# Control_Board.net
KiCad netlist of a schematic drawn in EAGLE
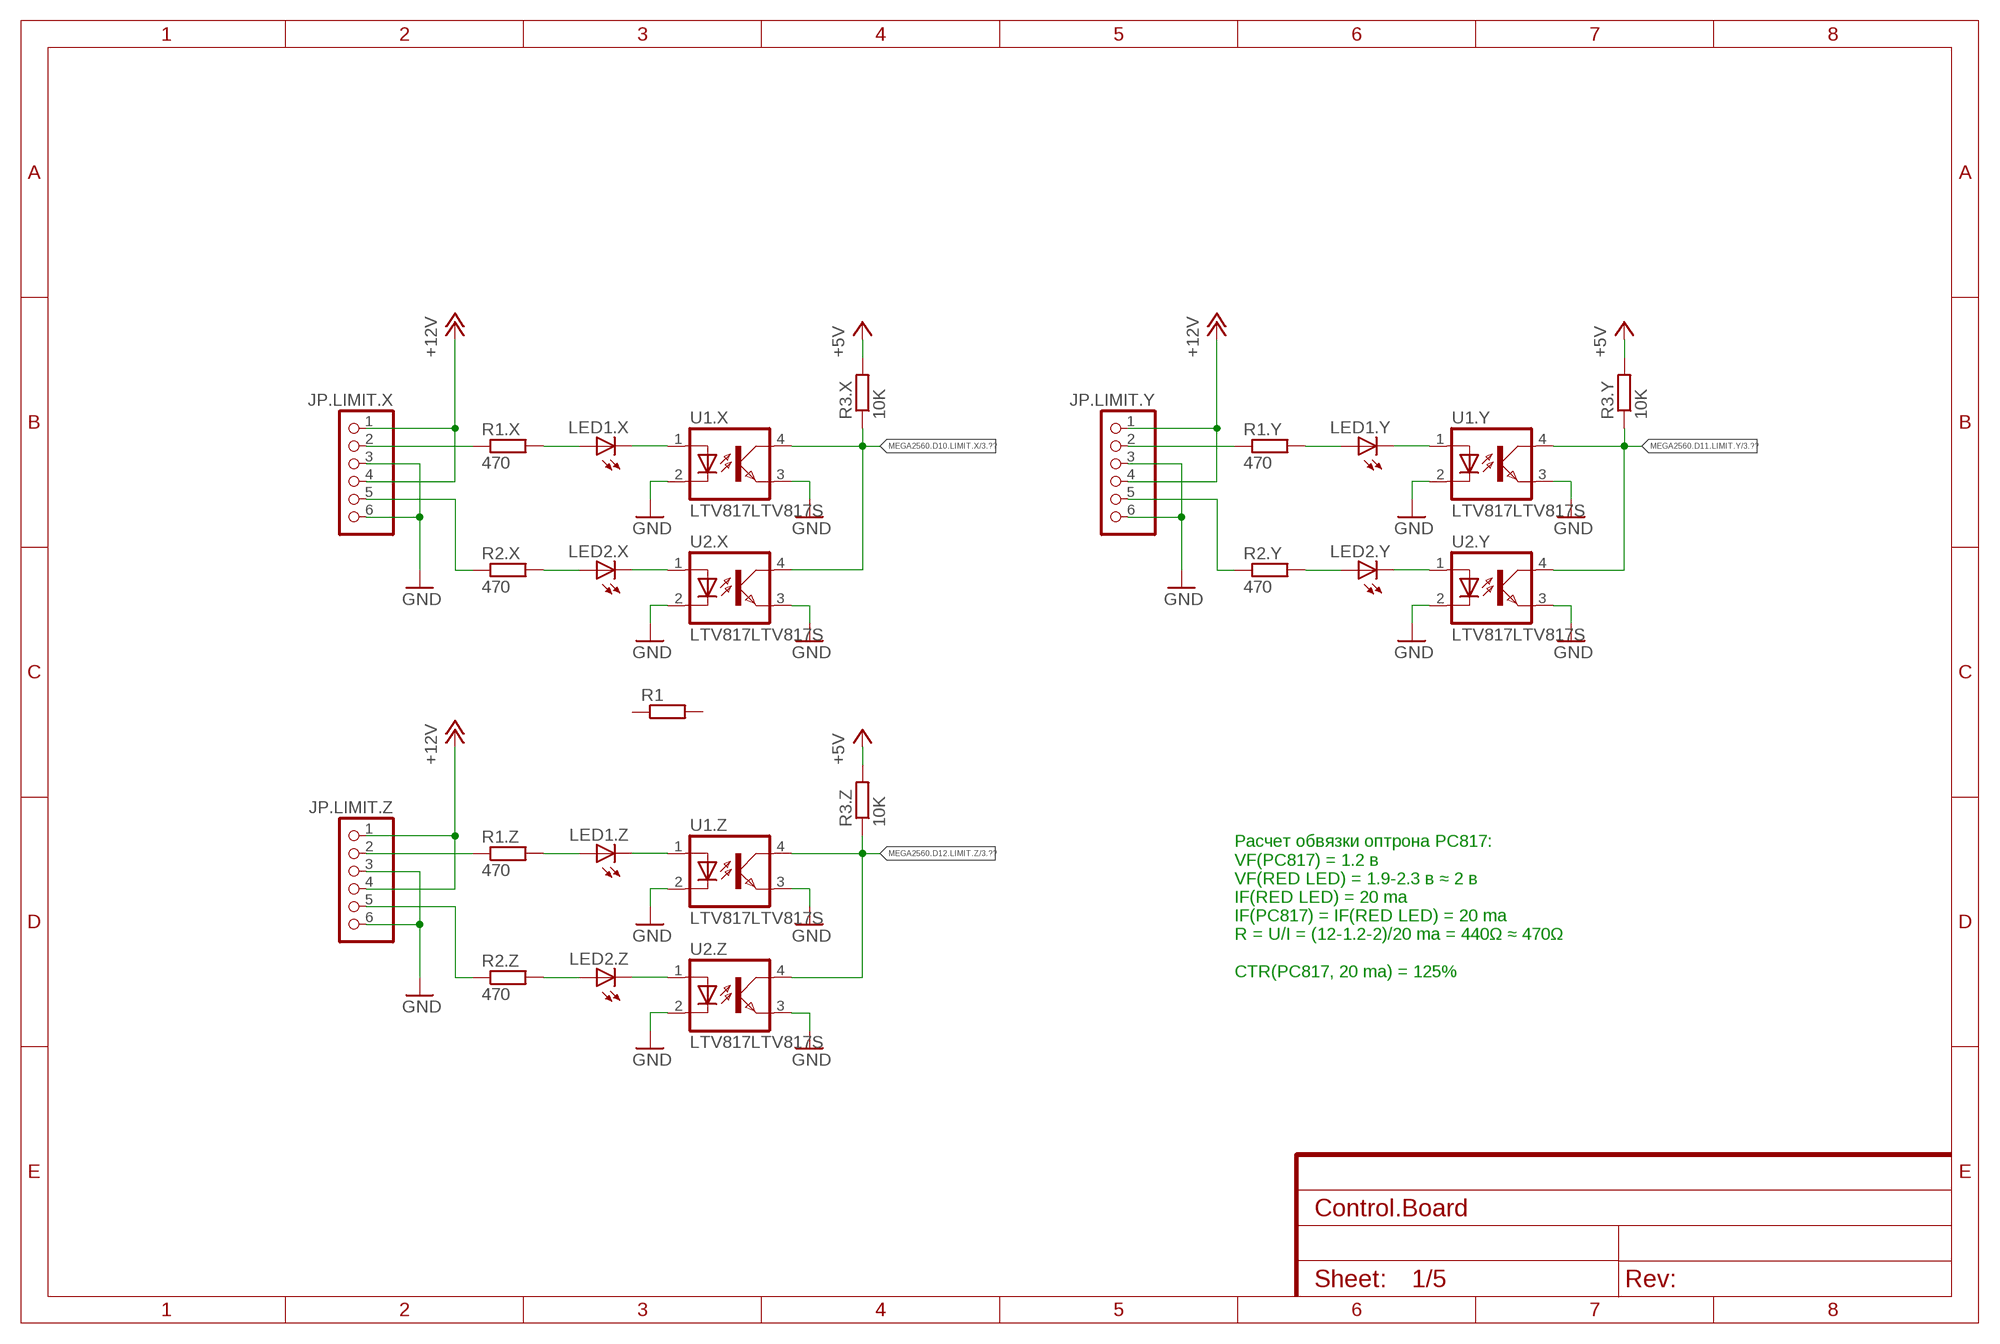
[diagram p0: schematic, sheet 1]
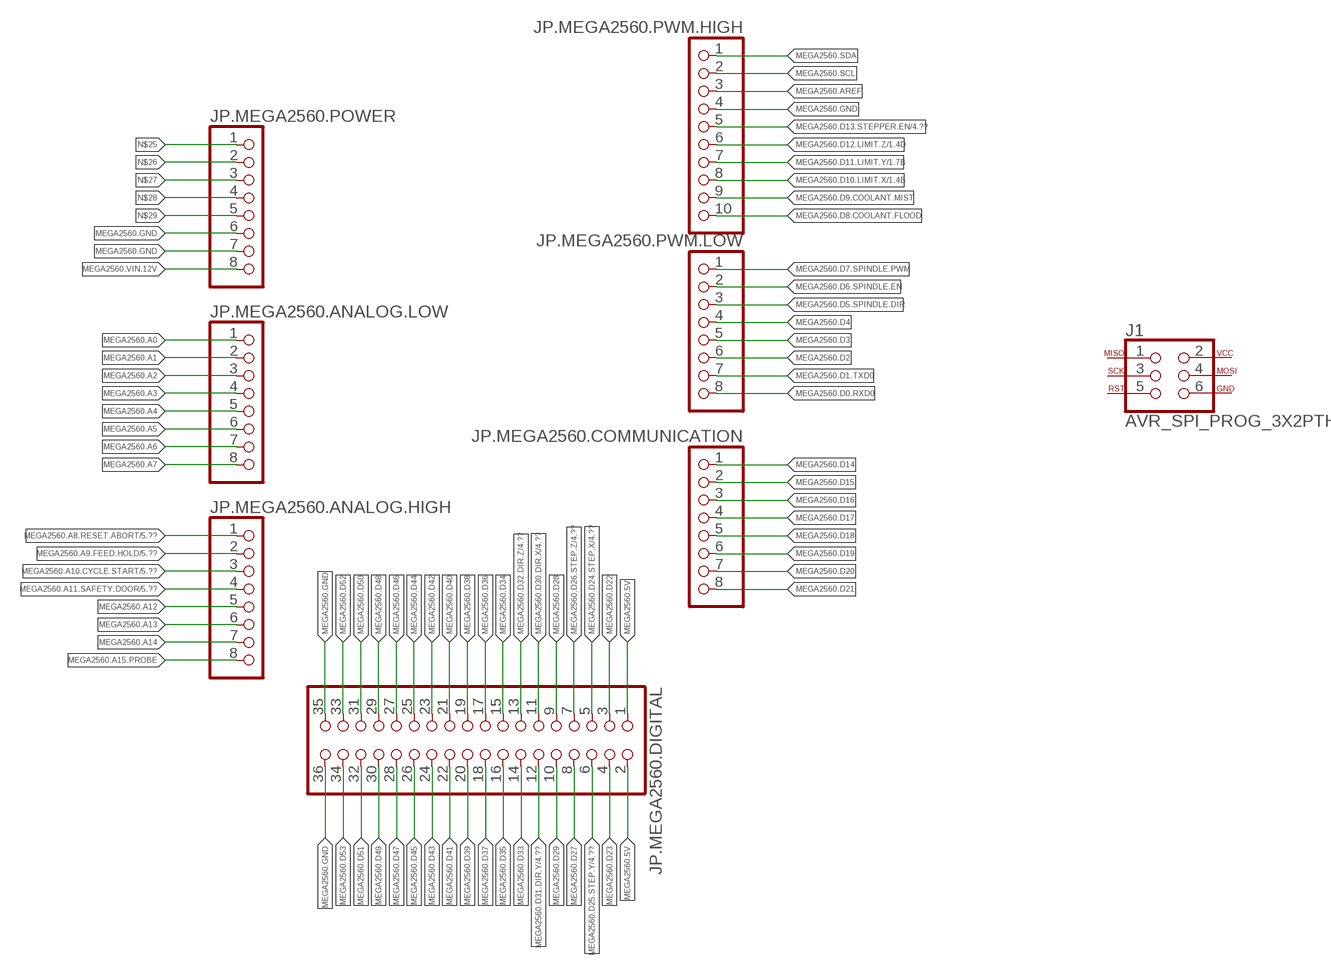
[diagram p1: schematic, sheet 3]
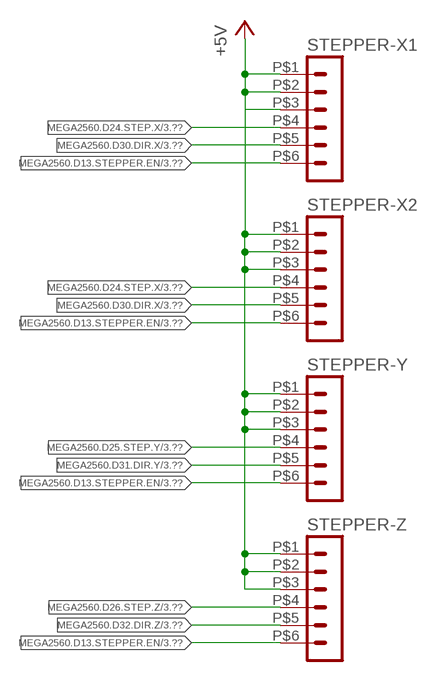
[diagram p2: schematic, sheet 4]
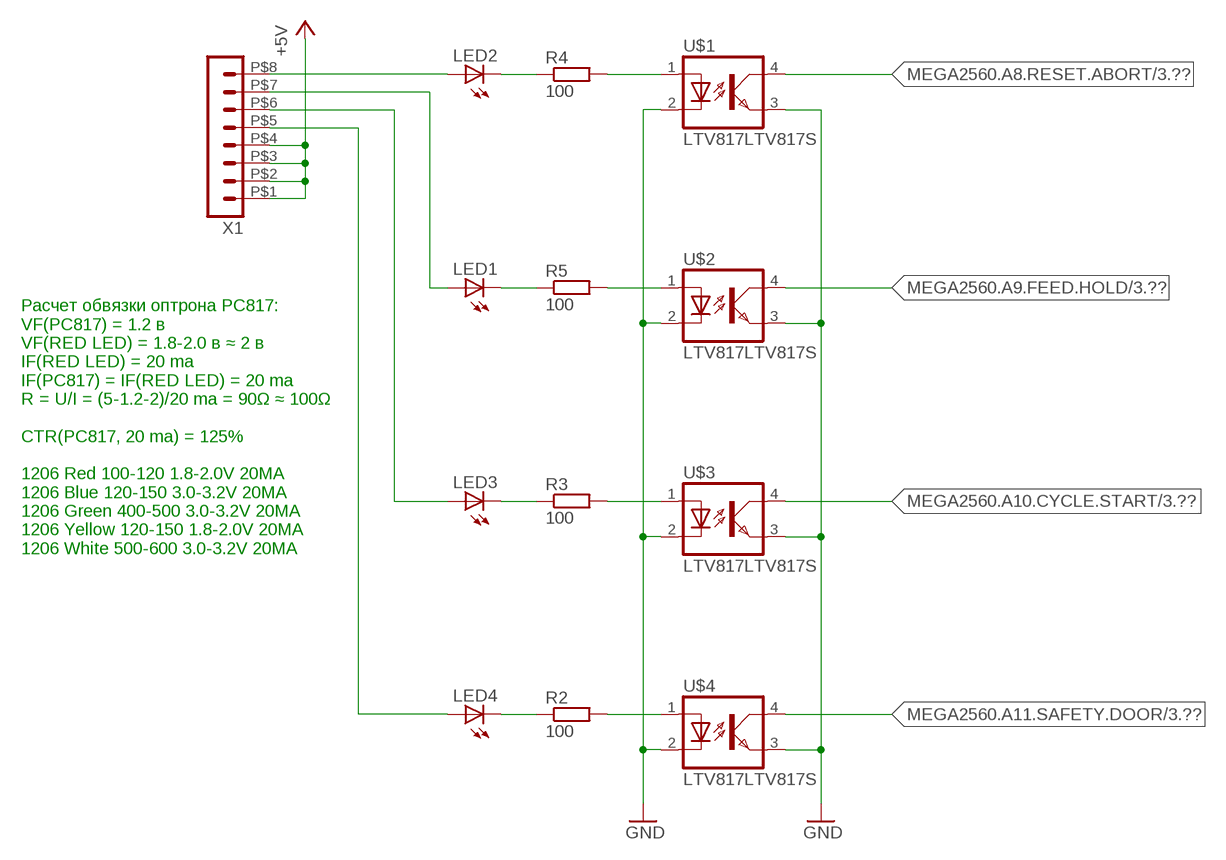
[diagram p3: schematic, sheet 5]

(export (version "E")
  (design (tool "Eeschema 10.0.6"))
  (components
    (comp (ref "LED1")
      (value "LEDCHIPLED_1206")
      (footprint "eagle-import:CHIPLED_1206")
      (libsource (lib "eagle-import") (part "LEDCHIPLED_1206"))
    )
    (comp (ref "LED2")
      (value "LEDCHIPLED_1206")
      (footprint "eagle-import:CHIPLED_1206")
      (libsource (lib "eagle-import") (part "LEDCHIPLED_1206"))
    )
    (comp (ref "LED3")
      (value "LEDCHIPLED_1206")
      (footprint "eagle-import:CHIPLED_1206")
      (libsource (lib "eagle-import") (part "LEDCHIPLED_1206"))
    )
    (comp (ref "LED4")
      (value "LEDCHIPLED_1206")
      (footprint "eagle-import:CHIPLED_1206")
      (libsource (lib "eagle-import") (part "LEDCHIPLED_1206"))
    )
    (comp (ref "R2")
      (value "100")
      (footprint "eagle-import:M1206")
      (libsource (lib "eagle-import") (part "R-EU_M1206"))
    )
    (comp (ref "R3")
      (value "100")
      (footprint "eagle-import:M1206")
      (libsource (lib "eagle-import") (part "R-EU_M1206"))
    )
    (comp (ref "R4")
      (value "100")
      (footprint "eagle-import:M1206")
      (libsource (lib "eagle-import") (part "R-EU_M1206"))
    )
    (comp (ref "R5")
      (value "100")
      (footprint "eagle-import:M1206")
      (libsource (lib "eagle-import") (part "R-EU_M1206"))
    )
    (comp (ref "U$1")
      (value "LTV817LTV817S")
      (footprint "eagle-import:DIL4-SMD")
      (libsource (lib "eagle-import") (part "LTV817LTV817S"))
    )
    (comp (ref "U$2")
      (value "LTV817LTV817S")
      (footprint "eagle-import:DIL4-SMD")
      (libsource (lib "eagle-import") (part "LTV817LTV817S"))
    )
    (comp (ref "U$3")
      (value "LTV817LTV817S")
      (footprint "eagle-import:DIL4-SMD")
      (libsource (lib "eagle-import") (part "LTV817LTV817S"))
    )
    (comp (ref "U$4")
      (value "LTV817LTV817S")
      (footprint "eagle-import:DIL4-SMD")
      (libsource (lib "eagle-import") (part "LTV817LTV817S"))
    )
    (comp (ref "X1")
      (value "HEADER_POS8_43045-0800")
      (footprint "eagle-import:43045-0800")
      (libsource (lib "eagle-import") (part "HEADER_POS8_?43045-0800"))
    )
    (comp (ref "J1")
      (value "AVR_SPI_PROG_3X2PTH")
      (footprint "eagle-import:2X3")
      (libsource (lib "eagle-import") (part "AVR_SPI_PROG_3X2PTH"))
    )
    (comp (ref "JP.MEGA2560.ANALOG.HIGH")
      (value "PINHD-1X8")
      (footprint "eagle-import:1X08")
      (libsource (lib "eagle-import") (part "PINHD-1X8"))
    )
    (comp (ref "JP.MEGA2560.ANALOG.LOW")
      (value "PINHD-1X8")
      (footprint "eagle-import:1X08")
      (libsource (lib "eagle-import") (part "PINHD-1X8"))
    )
    (comp (ref "JP.MEGA2560.COMMUNICATION")
      (value "PINHD-1X8")
      (footprint "eagle-import:1X08")
      (libsource (lib "eagle-import") (part "PINHD-1X8"))
    )
    (comp (ref "JP.MEGA2560.DIGITAL")
      (value "PINHD-2X18")
      (footprint "eagle-import:2X18")
      (libsource (lib "eagle-import") (part "PINHD-2X18"))
    )
    (comp (ref "JP.MEGA2560.POWER")
      (value "PINHD-1X8")
      (footprint "eagle-import:1X08")
      (libsource (lib "eagle-import") (part "PINHD-1X8"))
    )
    (comp (ref "JP.MEGA2560.PWM.HIGH")
      (value "PINHD-1X10")
      (footprint "eagle-import:1X10")
      (libsource (lib "eagle-import") (part "PINHD-1X10"))
    )
    (comp (ref "JP.MEGA2560.PWM.LOW")
      (value "PINHD-1X8")
      (footprint "eagle-import:1X08")
      (libsource (lib "eagle-import") (part "PINHD-1X8"))
    )
    (comp (ref "STEPPER-X1")
      (value "HEADER_POS6_43045-0600")
      (footprint "eagle-import:43045-0600")
      (libsource (lib "eagle-import") (part "HEADER_POS6_?43045-0600"))
    )
    (comp (ref "STEPPER-X2")
      (value "HEADER_POS6_43045-0600")
      (footprint "eagle-import:43045-0600")
      (libsource (lib "eagle-import") (part "HEADER_POS6_?43045-0600"))
    )
    (comp (ref "STEPPER-Y")
      (value "HEADER_POS6_43045-0600")
      (footprint "eagle-import:43045-0600")
      (libsource (lib "eagle-import") (part "HEADER_POS6_?43045-0600"))
    )
    (comp (ref "STEPPER-Z")
      (value "HEADER_POS6_43045-0600")
      (footprint "eagle-import:43045-0600")
      (libsource (lib "eagle-import") (part "HEADER_POS6_?43045-0600"))
    )
    (comp (ref "JP.LIMIT.X")
      (value "PINHD-1X6")
      (footprint "eagle-import:1X06")
      (libsource (lib "eagle-import") (part "PINHD-1X6"))
    )
    (comp (ref "JP.LIMIT.Y")
      (value "PINHD-1X6")
      (footprint "eagle-import:1X06")
      (libsource (lib "eagle-import") (part "PINHD-1X6"))
    )
    (comp (ref "JP.LIMIT.Z")
      (value "PINHD-1X6")
      (footprint "eagle-import:1X06")
      (libsource (lib "eagle-import") (part "PINHD-1X6"))
    )
    (comp (ref "LED1.X")
      (value "LEDCHIPLED_0805")
      (footprint "eagle-import:CHIPLED_0805")
      (libsource (lib "eagle-import") (part "LEDCHIPLED_0805"))
    )
    (comp (ref "LED1.Y")
      (value "LEDCHIPLED_0805")
      (footprint "eagle-import:CHIPLED_0805")
      (libsource (lib "eagle-import") (part "LEDCHIPLED_0805"))
    )
    (comp (ref "LED1.Z")
      (value "LEDCHIPLED_0805")
      (footprint "eagle-import:CHIPLED_0805")
      (libsource (lib "eagle-import") (part "LEDCHIPLED_0805"))
    )
    (comp (ref "LED2.X")
      (value "LEDCHIPLED_0805")
      (footprint "eagle-import:CHIPLED_0805")
      (libsource (lib "eagle-import") (part "LEDCHIPLED_0805"))
    )
    (comp (ref "LED2.Y")
      (value "LEDCHIPLED_0805")
      (footprint "eagle-import:CHIPLED_0805")
      (libsource (lib "eagle-import") (part "LEDCHIPLED_0805"))
    )
    (comp (ref "LED2.Z")
      (value "LEDCHIPLED_0805")
      (footprint "eagle-import:CHIPLED_0805")
      (libsource (lib "eagle-import") (part "LEDCHIPLED_0805"))
    )
    (comp (ref "R1")
      (value "R-EU_M1206")
      (footprint "eagle-import:M1206")
      (libsource (lib "eagle-import") (part "R-EU_M1206"))
    )
    (comp (ref "R1.X")
      (value "470")
      (footprint "eagle-import:M0805")
      (libsource (lib "eagle-import") (part "R-EU_M0805"))
    )
    (comp (ref "R1.Y")
      (value "470")
      (footprint "eagle-import:M0805")
      (libsource (lib "eagle-import") (part "R-EU_M0805"))
    )
    (comp (ref "R1.Z")
      (value "470")
      (footprint "eagle-import:M0805")
      (libsource (lib "eagle-import") (part "R-EU_M0805"))
    )
    (comp (ref "R2.X")
      (value "470")
      (footprint "eagle-import:M0805")
      (libsource (lib "eagle-import") (part "R-EU_M0805"))
    )
    (comp (ref "R2.Y")
      (value "470")
      (footprint "eagle-import:M0805")
      (libsource (lib "eagle-import") (part "R-EU_M0805"))
    )
    (comp (ref "R2.Z")
      (value "470")
      (footprint "eagle-import:M0805")
      (libsource (lib "eagle-import") (part "R-EU_M0805"))
    )
    (comp (ref "R3.X")
      (value "10K")
      (footprint "eagle-import:M0805")
      (libsource (lib "eagle-import") (part "R-EU_M0805"))
    )
    (comp (ref "R3.Y")
      (value "10K")
      (footprint "eagle-import:M0805")
      (libsource (lib "eagle-import") (part "R-EU_M0805"))
    )
    (comp (ref "R3.Z")
      (value "10K")
      (footprint "eagle-import:M0805")
      (libsource (lib "eagle-import") (part "R-EU_M0805"))
    )
    (comp (ref "U1.X")
      (value "LTV817LTV817S")
      (footprint "eagle-import:DIL4-SMD")
      (libsource (lib "eagle-import") (part "LTV817LTV817S"))
    )
    (comp (ref "U1.Y")
      (value "LTV817LTV817S")
      (footprint "eagle-import:DIL4-SMD")
      (libsource (lib "eagle-import") (part "LTV817LTV817S"))
    )
    (comp (ref "U1.Z")
      (value "LTV817LTV817S")
      (footprint "eagle-import:DIL4-SMD")
      (libsource (lib "eagle-import") (part "LTV817LTV817S"))
    )
    (comp (ref "U2.X")
      (value "LTV817LTV817S")
      (footprint "eagle-import:DIL4-SMD")
      (libsource (lib "eagle-import") (part "LTV817LTV817S"))
    )
    (comp (ref "U2.Y")
      (value "LTV817LTV817S")
      (footprint "eagle-import:DIL4-SMD")
      (libsource (lib "eagle-import") (part "LTV817LTV817S"))
    )
    (comp (ref "U2.Z")
      (value "LTV817LTV817S")
      (footprint "eagle-import:DIL4-SMD")
      (libsource (lib "eagle-import") (part "LTV817LTV817S"))
    )
  )
  (nets
    (net (code "1") (name "+5V") (class "Default")
      (node (ref "R3.X") (pin "2") (pinfunction "2_2") (pintype "passive"))
      (node (ref "R3.Y") (pin "2") (pinfunction "2_2") (pintype "passive"))
      (node (ref "R3.Z") (pin "2") (pinfunction "2_2") (pintype "passive"))
      (node (ref "STEPPER-X1") (pin "P$1") (pinfunction "1_P$1") (pintype "passive"))
      (node (ref "STEPPER-X1") (pin "P$2") (pinfunction "2_P$2") (pintype "passive"))
      (node (ref "STEPPER-X1") (pin "P$3") (pinfunction "3_P$3") (pintype "passive"))
      (node (ref "STEPPER-X2") (pin "P$1") (pinfunction "1_P$1") (pintype "passive"))
      (node (ref "STEPPER-X2") (pin "P$2") (pinfunction "2_P$2") (pintype "passive"))
      (node (ref "STEPPER-X2") (pin "P$3") (pinfunction "3_P$3") (pintype "passive"))
      (node (ref "STEPPER-Y") (pin "P$1") (pinfunction "1_P$1") (pintype "passive"))
      (node (ref "STEPPER-Y") (pin "P$2") (pinfunction "2_P$2") (pintype "passive"))
      (node (ref "STEPPER-Y") (pin "P$3") (pinfunction "3_P$3") (pintype "passive"))
      (node (ref "STEPPER-Z") (pin "P$1") (pinfunction "1_P$1") (pintype "passive"))
      (node (ref "STEPPER-Z") (pin "P$2") (pinfunction "2_P$2") (pintype "passive"))
      (node (ref "STEPPER-Z") (pin "P$3") (pinfunction "3_P$3") (pintype "passive"))
      (node (ref "X1") (pin "P$1") (pinfunction "1_P$1") (pintype "passive"))
      (node (ref "X1") (pin "P$2") (pinfunction "2_P$2") (pintype "passive"))
      (node (ref "X1") (pin "P$3") (pinfunction "3_P$3") (pintype "passive"))
      (node (ref "X1") (pin "P$4") (pinfunction "4_P$4") (pintype "passive"))
    )
    (net (code "2") (name "+12V") (class "Default")
      (node (ref "JP.LIMIT.X") (pin "1") (pinfunction "1_1") (pintype "passive"))
      (node (ref "JP.LIMIT.X") (pin "4") (pinfunction "4_4") (pintype "passive"))
      (node (ref "JP.LIMIT.Y") (pin "1") (pinfunction "1_1") (pintype "passive"))
      (node (ref "JP.LIMIT.Y") (pin "4") (pinfunction "4_4") (pintype "passive"))
      (node (ref "JP.LIMIT.Z") (pin "1") (pinfunction "1_1") (pintype "passive"))
      (node (ref "JP.LIMIT.Z") (pin "4") (pinfunction "4_4") (pintype "passive"))
    )
    (net (code "3") (name "GND") (class "Default")
      (node (ref "JP.LIMIT.X") (pin "3") (pinfunction "3_3") (pintype "passive"))
      (node (ref "JP.LIMIT.X") (pin "6") (pinfunction "6_6") (pintype "passive"))
      (node (ref "JP.LIMIT.Y") (pin "3") (pinfunction "3_3") (pintype "passive"))
      (node (ref "JP.LIMIT.Y") (pin "6") (pinfunction "6_6") (pintype "passive"))
      (node (ref "JP.LIMIT.Z") (pin "3") (pinfunction "3_3") (pintype "passive"))
      (node (ref "JP.LIMIT.Z") (pin "6") (pinfunction "6_6") (pintype "passive"))
      (node (ref "U$1") (pin "2") (pinfunction "C_2") (pintype "passive"))
      (node (ref "U$1") (pin "3") (pinfunction "EMIT_3") (pintype "passive"))
      (node (ref "U$2") (pin "2") (pinfunction "C_2") (pintype "passive"))
      (node (ref "U$2") (pin "3") (pinfunction "EMIT_3") (pintype "passive"))
      (node (ref "U$3") (pin "2") (pinfunction "C_2") (pintype "passive"))
      (node (ref "U$3") (pin "3") (pinfunction "EMIT_3") (pintype "passive"))
      (node (ref "U$4") (pin "2") (pinfunction "C_2") (pintype "passive"))
      (node (ref "U$4") (pin "3") (pinfunction "EMIT_3") (pintype "passive"))
      (node (ref "U1.X") (pin "2") (pinfunction "C_2") (pintype "passive"))
      (node (ref "U1.X") (pin "3") (pinfunction "EMIT_3") (pintype "passive"))
      (node (ref "U1.Y") (pin "2") (pinfunction "C_2") (pintype "passive"))
      (node (ref "U1.Y") (pin "3") (pinfunction "EMIT_3") (pintype "passive"))
      (node (ref "U1.Z") (pin "2") (pinfunction "C_2") (pintype "passive"))
      (node (ref "U1.Z") (pin "3") (pinfunction "EMIT_3") (pintype "passive"))
      (node (ref "U2.X") (pin "2") (pinfunction "C_2") (pintype "passive"))
      (node (ref "U2.X") (pin "3") (pinfunction "EMIT_3") (pintype "passive"))
      (node (ref "U2.Y") (pin "2") (pinfunction "C_2") (pintype "passive"))
      (node (ref "U2.Y") (pin "3") (pinfunction "EMIT_3") (pintype "passive"))
      (node (ref "U2.Z") (pin "2") (pinfunction "C_2") (pintype "passive"))
      (node (ref "U2.Z") (pin "3") (pinfunction "EMIT_3") (pintype "passive"))
    )
    (net (code "4") (name "MEGA2560.5V") (class "Default")
      (node (ref "JP.MEGA2560.DIGITAL") (pin "1") (pinfunction "1_1") (pintype "passive"))
      (node (ref "JP.MEGA2560.DIGITAL") (pin "2") (pinfunction "2_2") (pintype "passive"))
    )
    (net (code "5") (name "MEGA2560.A0") (class "Default")
      (node (ref "JP.MEGA2560.ANALOG.LOW") (pin "1") (pinfunction "1_1") (pintype "passive"))
    )
    (net (code "6") (name "MEGA2560.A1") (class "Default")
      (node (ref "JP.MEGA2560.ANALOG.LOW") (pin "2") (pinfunction "2_2") (pintype "passive"))
    )
    (net (code "7") (name "MEGA2560.A2") (class "Default")
      (node (ref "JP.MEGA2560.ANALOG.LOW") (pin "3") (pinfunction "3_3") (pintype "passive"))
    )
    (net (code "8") (name "MEGA2560.A3") (class "Default")
      (node (ref "JP.MEGA2560.ANALOG.LOW") (pin "4") (pinfunction "4_4") (pintype "passive"))
    )
    (net (code "9") (name "MEGA2560.A4") (class "Default")
      (node (ref "JP.MEGA2560.ANALOG.LOW") (pin "5") (pinfunction "5_5") (pintype "passive"))
    )
    (net (code "10") (name "MEGA2560.A5") (class "Default")
      (node (ref "JP.MEGA2560.ANALOG.LOW") (pin "6") (pinfunction "6_6") (pintype "passive"))
    )
    (net (code "11") (name "MEGA2560.A6") (class "Default")
      (node (ref "JP.MEGA2560.ANALOG.LOW") (pin "7") (pinfunction "7_7") (pintype "passive"))
    )
    (net (code "12") (name "MEGA2560.A7") (class "Default")
      (node (ref "JP.MEGA2560.ANALOG.LOW") (pin "8") (pinfunction "8_8") (pintype "passive"))
    )
    (net (code "13") (name "MEGA2560.A8.RESET.ABORT") (class "Default")
      (node (ref "JP.MEGA2560.ANALOG.HIGH") (pin "1") (pinfunction "1_1") (pintype "passive"))
      (node (ref "U$1") (pin "4") (pinfunction "COL_4") (pintype "passive"))
    )
    (net (code "14") (name "MEGA2560.A9.FEED.HOLD") (class "Default")
      (node (ref "JP.MEGA2560.ANALOG.HIGH") (pin "2") (pinfunction "2_2") (pintype "passive"))
      (node (ref "U$2") (pin "4") (pinfunction "COL_4") (pintype "passive"))
    )
    (net (code "15") (name "MEGA2560.A10.CYCLE.START") (class "Default")
      (node (ref "JP.MEGA2560.ANALOG.HIGH") (pin "3") (pinfunction "3_3") (pintype "passive"))
      (node (ref "U$3") (pin "4") (pinfunction "COL_4") (pintype "passive"))
    )
    (net (code "16") (name "MEGA2560.A11.SAFETY.DOOR") (class "Default")
      (node (ref "JP.MEGA2560.ANALOG.HIGH") (pin "4") (pinfunction "4_4") (pintype "passive"))
      (node (ref "U$4") (pin "4") (pinfunction "COL_4") (pintype "passive"))
    )
    (net (code "17") (name "MEGA2560.A12") (class "Default")
      (node (ref "JP.MEGA2560.ANALOG.HIGH") (pin "5") (pinfunction "5_5") (pintype "passive"))
    )
    (net (code "18") (name "MEGA2560.A13") (class "Default")
      (node (ref "JP.MEGA2560.ANALOG.HIGH") (pin "6") (pinfunction "6_6") (pintype "passive"))
    )
    (net (code "19") (name "MEGA2560.A14") (class "Default")
      (node (ref "JP.MEGA2560.ANALOG.HIGH") (pin "7") (pinfunction "7_7") (pintype "passive"))
    )
    (net (code "20") (name "MEGA2560.A15.PROBE") (class "Default")
      (node (ref "JP.MEGA2560.ANALOG.HIGH") (pin "8") (pinfunction "8_8") (pintype "passive"))
    )
    (net (code "21") (name "MEGA2560.AREF") (class "Default")
      (node (ref "JP.MEGA2560.PWM.HIGH") (pin "3") (pinfunction "3_3") (pintype "passive"))
    )
    (net (code "22") (name "MEGA2560.D0.RXD0") (class "Default")
      (node (ref "JP.MEGA2560.PWM.LOW") (pin "8") (pinfunction "8_8") (pintype "passive"))
    )
    (net (code "23") (name "MEGA2560.D1.TXD0") (class "Default")
      (node (ref "JP.MEGA2560.PWM.LOW") (pin "7") (pinfunction "7_7") (pintype "passive"))
    )
    (net (code "24") (name "MEGA2560.D2") (class "Default")
      (node (ref "JP.MEGA2560.PWM.LOW") (pin "6") (pinfunction "6_6") (pintype "passive"))
    )
    (net (code "25") (name "MEGA2560.D3") (class "Default")
      (node (ref "JP.MEGA2560.PWM.LOW") (pin "5") (pinfunction "5_5") (pintype "passive"))
    )
    (net (code "26") (name "MEGA2560.D4") (class "Default")
      (node (ref "JP.MEGA2560.PWM.LOW") (pin "4") (pinfunction "4_4") (pintype "passive"))
    )
    (net (code "27") (name "MEGA2560.D5.SPINDLE.DIR") (class "Default")
      (node (ref "JP.MEGA2560.PWM.LOW") (pin "3") (pinfunction "3_3") (pintype "passive"))
    )
    (net (code "28") (name "MEGA2560.D6.SPINDLE.EN") (class "Default")
      (node (ref "JP.MEGA2560.PWM.LOW") (pin "2") (pinfunction "2_2") (pintype "passive"))
    )
    (net (code "29") (name "MEGA2560.D7.SPINDLE.PWM") (class "Default")
      (node (ref "JP.MEGA2560.PWM.LOW") (pin "1") (pinfunction "1_1") (pintype "passive"))
    )
    (net (code "30") (name "MEGA2560.D8.COOLANT.FLOOD") (class "Default")
      (node (ref "JP.MEGA2560.PWM.HIGH") (pin "10") (pinfunction "10_10") (pintype "passive"))
    )
    (net (code "31") (name "MEGA2560.D9.COOLANT.MIST") (class "Default")
      (node (ref "JP.MEGA2560.PWM.HIGH") (pin "9") (pinfunction "9_9") (pintype "passive"))
    )
    (net (code "32") (name "MEGA2560.D10.LIMIT.X") (class "Default")
      (node (ref "JP.MEGA2560.PWM.HIGH") (pin "8") (pinfunction "8_8") (pintype "passive"))
      (node (ref "R3.X") (pin "1") (pinfunction "1_1") (pintype "passive"))
      (node (ref "U1.X") (pin "4") (pinfunction "COL_4") (pintype "passive"))
      (node (ref "U2.X") (pin "4") (pinfunction "COL_4") (pintype "passive"))
    )
    (net (code "33") (name "MEGA2560.D11.LIMIT.Y") (class "Default")
      (node (ref "JP.MEGA2560.PWM.HIGH") (pin "7") (pinfunction "7_7") (pintype "passive"))
      (node (ref "R3.Y") (pin "1") (pinfunction "1_1") (pintype "passive"))
      (node (ref "U1.Y") (pin "4") (pinfunction "COL_4") (pintype "passive"))
      (node (ref "U2.Y") (pin "4") (pinfunction "COL_4") (pintype "passive"))
    )
    (net (code "34") (name "MEGA2560.D12.LIMIT.Z") (class "Default")
      (node (ref "JP.MEGA2560.PWM.HIGH") (pin "6") (pinfunction "6_6") (pintype "passive"))
      (node (ref "R3.Z") (pin "1") (pinfunction "1_1") (pintype "passive"))
      (node (ref "U1.Z") (pin "4") (pinfunction "COL_4") (pintype "passive"))
      (node (ref "U2.Z") (pin "4") (pinfunction "COL_4") (pintype "passive"))
    )
    (net (code "35") (name "MEGA2560.D13.STEPPER.EN") (class "Default")
      (node (ref "JP.MEGA2560.PWM.HIGH") (pin "5") (pinfunction "5_5") (pintype "passive"))
      (node (ref "STEPPER-X1") (pin "P$6") (pinfunction "6_P$6") (pintype "passive"))
      (node (ref "STEPPER-X2") (pin "P$6") (pinfunction "6_P$6") (pintype "passive"))
      (node (ref "STEPPER-Y") (pin "P$6") (pinfunction "6_P$6") (pintype "passive"))
      (node (ref "STEPPER-Z") (pin "P$6") (pinfunction "6_P$6") (pintype "passive"))
    )
    (net (code "36") (name "MEGA2560.D14") (class "Default")
      (node (ref "JP.MEGA2560.COMMUNICATION") (pin "1") (pinfunction "1_1") (pintype "passive"))
    )
    (net (code "37") (name "MEGA2560.D15") (class "Default")
      (node (ref "JP.MEGA2560.COMMUNICATION") (pin "2") (pinfunction "2_2") (pintype "passive"))
    )
    (net (code "38") (name "MEGA2560.D16") (class "Default")
      (node (ref "JP.MEGA2560.COMMUNICATION") (pin "3") (pinfunction "3_3") (pintype "passive"))
    )
    (net (code "39") (name "MEGA2560.D17") (class "Default")
      (node (ref "JP.MEGA2560.COMMUNICATION") (pin "4") (pinfunction "4_4") (pintype "passive"))
    )
    (net (code "40") (name "MEGA2560.D18") (class "Default")
      (node (ref "JP.MEGA2560.COMMUNICATION") (pin "5") (pinfunction "5_5") (pintype "passive"))
    )
    (net (code "41") (name "MEGA2560.D19") (class "Default")
      (node (ref "JP.MEGA2560.COMMUNICATION") (pin "6") (pinfunction "6_6") (pintype "passive"))
    )
    (net (code "42") (name "MEGA2560.D20") (class "Default")
      (node (ref "JP.MEGA2560.COMMUNICATION") (pin "7") (pinfunction "7_7") (pintype "passive"))
    )
    (net (code "43") (name "MEGA2560.D21") (class "Default")
      (node (ref "JP.MEGA2560.COMMUNICATION") (pin "8") (pinfunction "8_8") (pintype "passive"))
    )
    (net (code "44") (name "MEGA2560.D22") (class "Default")
      (node (ref "JP.MEGA2560.DIGITAL") (pin "3") (pinfunction "3_3") (pintype "passive"))
    )
    (net (code "45") (name "MEGA2560.D23") (class "Default")
      (node (ref "JP.MEGA2560.DIGITAL") (pin "4") (pinfunction "4_4") (pintype "passive"))
    )
    (net (code "46") (name "MEGA2560.D24.STEP.X") (class "Default")
      (node (ref "JP.MEGA2560.DIGITAL") (pin "5") (pinfunction "5_5") (pintype "passive"))
      (node (ref "STEPPER-X1") (pin "P$4") (pinfunction "4_P$4") (pintype "passive"))
      (node (ref "STEPPER-X2") (pin "P$4") (pinfunction "4_P$4") (pintype "passive"))
    )
    (net (code "47") (name "MEGA2560.D25.STEP.Y") (class "Default")
      (node (ref "JP.MEGA2560.DIGITAL") (pin "6") (pinfunction "6_6") (pintype "passive"))
      (node (ref "STEPPER-Y") (pin "P$4") (pinfunction "4_P$4") (pintype "passive"))
    )
    (net (code "48") (name "MEGA2560.D26.STEP.Z") (class "Default")
      (node (ref "JP.MEGA2560.DIGITAL") (pin "7") (pinfunction "7_7") (pintype "passive"))
      (node (ref "STEPPER-Z") (pin "P$4") (pinfunction "4_P$4") (pintype "passive"))
    )
    (net (code "49") (name "MEGA2560.D27") (class "Default")
      (node (ref "JP.MEGA2560.DIGITAL") (pin "8") (pinfunction "8_8") (pintype "passive"))
    )
    (net (code "50") (name "MEGA2560.D28") (class "Default")
      (node (ref "JP.MEGA2560.DIGITAL") (pin "9") (pinfunction "9_9") (pintype "passive"))
    )
    (net (code "51") (name "MEGA2560.D29") (class "Default")
      (node (ref "JP.MEGA2560.DIGITAL") (pin "10") (pinfunction "10_10") (pintype "passive"))
    )
    (net (code "52") (name "MEGA2560.D30.DIR.X") (class "Default")
      (node (ref "JP.MEGA2560.DIGITAL") (pin "11") (pinfunction "11_11") (pintype "passive"))
      (node (ref "STEPPER-X1") (pin "P$5") (pinfunction "5_P$5") (pintype "passive"))
      (node (ref "STEPPER-X2") (pin "P$5") (pinfunction "5_P$5") (pintype "passive"))
    )
    (net (code "53") (name "MEGA2560.D31.DIR.Y") (class "Default")
      (node (ref "JP.MEGA2560.DIGITAL") (pin "12") (pinfunction "12_12") (pintype "passive"))
      (node (ref "STEPPER-Y") (pin "P$5") (pinfunction "5_P$5") (pintype "passive"))
    )
    (net (code "54") (name "MEGA2560.D32.DIR.Z") (class "Default")
      (node (ref "JP.MEGA2560.DIGITAL") (pin "13") (pinfunction "13_13") (pintype "passive"))
      (node (ref "STEPPER-Z") (pin "P$5") (pinfunction "5_P$5") (pintype "passive"))
    )
    (net (code "55") (name "MEGA2560.D33") (class "Default")
      (node (ref "JP.MEGA2560.DIGITAL") (pin "14") (pinfunction "14_14") (pintype "passive"))
    )
    (net (code "56") (name "MEGA2560.D34") (class "Default")
      (node (ref "JP.MEGA2560.DIGITAL") (pin "15") (pinfunction "15_15") (pintype "passive"))
    )
    (net (code "57") (name "MEGA2560.D35") (class "Default")
      (node (ref "JP.MEGA2560.DIGITAL") (pin "16") (pinfunction "16_16") (pintype "passive"))
    )
    (net (code "58") (name "MEGA2560.D36") (class "Default")
      (node (ref "JP.MEGA2560.DIGITAL") (pin "17") (pinfunction "17_17") (pintype "passive"))
    )
    (net (code "59") (name "MEGA2560.D37") (class "Default")
      (node (ref "JP.MEGA2560.DIGITAL") (pin "18") (pinfunction "18_18") (pintype "passive"))
    )
    (net (code "60") (name "MEGA2560.D38") (class "Default")
      (node (ref "JP.MEGA2560.DIGITAL") (pin "19") (pinfunction "19_19") (pintype "passive"))
    )
    (net (code "61") (name "MEGA2560.D39") (class "Default")
      (node (ref "JP.MEGA2560.DIGITAL") (pin "20") (pinfunction "20_20") (pintype "passive"))
    )
    (net (code "62") (name "MEGA2560.D40") (class "Default")
      (node (ref "JP.MEGA2560.DIGITAL") (pin "21") (pinfunction "21_21") (pintype "passive"))
    )
    (net (code "63") (name "MEGA2560.D41") (class "Default")
      (node (ref "JP.MEGA2560.DIGITAL") (pin "22") (pinfunction "22_22") (pintype "passive"))
    )
    (net (code "64") (name "MEGA2560.D42") (class "Default")
      (node (ref "JP.MEGA2560.DIGITAL") (pin "23") (pinfunction "23_23") (pintype "passive"))
    )
    (net (code "65") (name "MEGA2560.D43") (class "Default")
      (node (ref "JP.MEGA2560.DIGITAL") (pin "24") (pinfunction "24_24") (pintype "passive"))
    )
    (net (code "66") (name "MEGA2560.D44") (class "Default")
      (node (ref "JP.MEGA2560.DIGITAL") (pin "25") (pinfunction "25_25") (pintype "passive"))
    )
    (net (code "67") (name "MEGA2560.D45") (class "Default")
      (node (ref "JP.MEGA2560.DIGITAL") (pin "26") (pinfunction "26_26") (pintype "passive"))
    )
    (net (code "68") (name "MEGA2560.D46") (class "Default")
      (node (ref "JP.MEGA2560.DIGITAL") (pin "27") (pinfunction "27_27") (pintype "passive"))
    )
    (net (code "69") (name "MEGA2560.D47") (class "Default")
      (node (ref "JP.MEGA2560.DIGITAL") (pin "28") (pinfunction "28_28") (pintype "passive"))
    )
    (net (code "70") (name "MEGA2560.D48") (class "Default")
      (node (ref "JP.MEGA2560.DIGITAL") (pin "29") (pinfunction "29_29") (pintype "passive"))
    )
    (net (code "71") (name "MEGA2560.D49") (class "Default")
      (node (ref "JP.MEGA2560.DIGITAL") (pin "30") (pinfunction "30_30") (pintype "passive"))
    )
    (net (code "72") (name "MEGA2560.D50") (class "Default")
      (node (ref "JP.MEGA2560.DIGITAL") (pin "31") (pinfunction "31_31") (pintype "passive"))
    )
    (net (code "73") (name "MEGA2560.D51") (class "Default")
      (node (ref "JP.MEGA2560.DIGITAL") (pin "32") (pinfunction "32_32") (pintype "passive"))
    )
    (net (code "74") (name "MEGA2560.D52") (class "Default")
      (node (ref "JP.MEGA2560.DIGITAL") (pin "33") (pinfunction "33_33") (pintype "passive"))
    )
    (net (code "75") (name "MEGA2560.D53") (class "Default")
      (node (ref "JP.MEGA2560.DIGITAL") (pin "34") (pinfunction "34_34") (pintype "passive"))
    )
    (net (code "76") (name "MEGA2560.GND") (class "Default")
      (node (ref "JP.MEGA2560.DIGITAL") (pin "35") (pinfunction "35_35") (pintype "passive"))
      (node (ref "JP.MEGA2560.DIGITAL") (pin "36") (pinfunction "36_36") (pintype "passive"))
      (node (ref "JP.MEGA2560.POWER") (pin "6") (pinfunction "6_6") (pintype "passive"))
      (node (ref "JP.MEGA2560.POWER") (pin "7") (pinfunction "7_7") (pintype "passive"))
      (node (ref "JP.MEGA2560.PWM.HIGH") (pin "4") (pinfunction "4_4") (pintype "passive"))
    )
    (net (code "77") (name "MEGA2560.SCL") (class "Default")
      (node (ref "JP.MEGA2560.PWM.HIGH") (pin "2") (pinfunction "2_2") (pintype "passive"))
    )
    (net (code "78") (name "MEGA2560.SDA") (class "Default")
      (node (ref "JP.MEGA2560.PWM.HIGH") (pin "1") (pinfunction "1_1") (pintype "passive"))
    )
    (net (code "79") (name "MEGA2560.VIN.12V") (class "Default")
      (node (ref "JP.MEGA2560.POWER") (pin "8") (pinfunction "8_8") (pintype "passive"))
    )
    (net (code "80") (name "N$25") (class "Default")
      (node (ref "JP.MEGA2560.POWER") (pin "1") (pinfunction "1_1") (pintype "passive"))
    )
    (net (code "81") (name "N$26") (class "Default")
      (node (ref "JP.MEGA2560.POWER") (pin "2") (pinfunction "2_2") (pintype "passive"))
    )
    (net (code "82") (name "N$27") (class "Default")
      (node (ref "JP.MEGA2560.POWER") (pin "3") (pinfunction "3_3") (pintype "passive"))
    )
    (net (code "83") (name "N$28") (class "Default")
      (node (ref "JP.MEGA2560.POWER") (pin "4") (pinfunction "4_4") (pintype "passive"))
    )
    (net (code "84") (name "N$29") (class "Default")
      (node (ref "JP.MEGA2560.POWER") (pin "5") (pinfunction "5_5") (pintype "passive"))
    )
    (net (code "85") (name "Net-(JP.LIMIT.X-Pad2)") (class "Default")
      (node (ref "JP.LIMIT.X") (pin "2") (pinfunction "2_2") (pintype "passive"))
      (node (ref "R1.X") (pin "1") (pinfunction "1_1") (pintype "passive"))
    )
    (net (code "86") (name "Net-(JP.LIMIT.X-Pad5)") (class "Default")
      (node (ref "JP.LIMIT.X") (pin "5") (pinfunction "5_5") (pintype "passive"))
      (node (ref "R2.X") (pin "1") (pinfunction "1_1") (pintype "passive"))
    )
    (net (code "87") (name "Net-(JP.LIMIT.Y-Pad2)") (class "Default")
      (node (ref "JP.LIMIT.Y") (pin "2") (pinfunction "2_2") (pintype "passive"))
      (node (ref "R1.Y") (pin "1") (pinfunction "1_1") (pintype "passive"))
    )
    (net (code "88") (name "Net-(JP.LIMIT.Y-Pad5)") (class "Default")
      (node (ref "JP.LIMIT.Y") (pin "5") (pinfunction "5_5") (pintype "passive"))
      (node (ref "R2.Y") (pin "1") (pinfunction "1_1") (pintype "passive"))
    )
    (net (code "89") (name "Net-(JP.LIMIT.Z-Pad2)") (class "Default")
      (node (ref "JP.LIMIT.Z") (pin "2") (pinfunction "2_2") (pintype "passive"))
      (node (ref "R1.Z") (pin "1") (pinfunction "1_1") (pintype "passive"))
    )
    (net (code "90") (name "Net-(JP.LIMIT.Z-Pad5)") (class "Default")
      (node (ref "JP.LIMIT.Z") (pin "5") (pinfunction "5_5") (pintype "passive"))
      (node (ref "R2.Z") (pin "1") (pinfunction "1_1") (pintype "passive"))
    )
    (net (code "91") (name "Net-(LED1-PadC)") (class "Default")
      (node (ref "LED1") (pin "C") (pinfunction "C_C") (pintype "passive"))
      (node (ref "R5") (pin "1") (pinfunction "1_1") (pintype "passive"))
    )
    (net (code "92") (name "Net-(LED1.X-PadA)") (class "Default")
      (node (ref "LED1.X") (pin "A") (pinfunction "A_A") (pintype "passive"))
      (node (ref "R1.X") (pin "2") (pinfunction "2_2") (pintype "passive"))
    )
    (net (code "93") (name "Net-(LED1.Y-PadA)") (class "Default")
      (node (ref "LED1.Y") (pin "A") (pinfunction "A_A") (pintype "passive"))
      (node (ref "R1.Y") (pin "2") (pinfunction "2_2") (pintype "passive"))
    )
    (net (code "94") (name "Net-(LED1.Z-PadA)") (class "Default")
      (node (ref "LED1.Z") (pin "A") (pinfunction "A_A") (pintype "passive"))
      (node (ref "R1.Z") (pin "2") (pinfunction "2_2") (pintype "passive"))
    )
    (net (code "95") (name "Net-(LED2-PadC)") (class "Default")
      (node (ref "LED2") (pin "C") (pinfunction "C_C") (pintype "passive"))
      (node (ref "R4") (pin "1") (pinfunction "1_1") (pintype "passive"))
    )
    (net (code "96") (name "Net-(LED2.X-PadA)") (class "Default")
      (node (ref "LED2.X") (pin "A") (pinfunction "A_A") (pintype "passive"))
      (node (ref "R2.X") (pin "2") (pinfunction "2_2") (pintype "passive"))
    )
    (net (code "97") (name "Net-(LED2.Y-PadA)") (class "Default")
      (node (ref "LED2.Y") (pin "A") (pinfunction "A_A") (pintype "passive"))
      (node (ref "R2.Y") (pin "2") (pinfunction "2_2") (pintype "passive"))
    )
    (net (code "98") (name "Net-(LED2.Z-PadA)") (class "Default")
      (node (ref "LED2.Z") (pin "A") (pinfunction "A_A") (pintype "passive"))
      (node (ref "R2.Z") (pin "2") (pinfunction "2_2") (pintype "passive"))
    )
    (net (code "99") (name "Net-(LED3-PadC)") (class "Default")
      (node (ref "LED3") (pin "C") (pinfunction "C_C") (pintype "passive"))
      (node (ref "R3") (pin "1") (pinfunction "1_1") (pintype "passive"))
    )
    (net (code "100") (name "Net-(LED4-PadC)") (class "Default")
      (node (ref "LED4") (pin "C") (pinfunction "C_C") (pintype "passive"))
      (node (ref "R2") (pin "1") (pinfunction "1_1") (pintype "passive"))
    )
    (net (code "101") (name "Net-(U$1-A)") (class "Default")
      (node (ref "R4") (pin "2") (pinfunction "2_2") (pintype "passive"))
      (node (ref "U$1") (pin "1") (pinfunction "A_1") (pintype "passive"))
    )
    (net (code "102") (name "Net-(U$2-A)") (class "Default")
      (node (ref "R5") (pin "2") (pinfunction "2_2") (pintype "passive"))
      (node (ref "U$2") (pin "1") (pinfunction "A_1") (pintype "passive"))
    )
    (net (code "103") (name "Net-(U$3-A)") (class "Default")
      (node (ref "R3") (pin "2") (pinfunction "2_2") (pintype "passive"))
      (node (ref "U$3") (pin "1") (pinfunction "A_1") (pintype "passive"))
    )
    (net (code "104") (name "Net-(U$4-A)") (class "Default")
      (node (ref "R2") (pin "2") (pinfunction "2_2") (pintype "passive"))
      (node (ref "U$4") (pin "1") (pinfunction "A_1") (pintype "passive"))
    )
    (net (code "105") (name "Net-(U1.X-A)") (class "Default")
      (node (ref "LED1.X") (pin "C") (pinfunction "C_C") (pintype "passive"))
      (node (ref "U1.X") (pin "1") (pinfunction "A_1") (pintype "passive"))
    )
    (net (code "106") (name "Net-(U1.Y-A)") (class "Default")
      (node (ref "LED1.Y") (pin "C") (pinfunction "C_C") (pintype "passive"))
      (node (ref "U1.Y") (pin "1") (pinfunction "A_1") (pintype "passive"))
    )
    (net (code "107") (name "Net-(U1.Z-A)") (class "Default")
      (node (ref "LED1.Z") (pin "C") (pinfunction "C_C") (pintype "passive"))
      (node (ref "U1.Z") (pin "1") (pinfunction "A_1") (pintype "passive"))
    )
    (net (code "108") (name "Net-(U2.X-A)") (class "Default")
      (node (ref "LED2.X") (pin "C") (pinfunction "C_C") (pintype "passive"))
      (node (ref "U2.X") (pin "1") (pinfunction "A_1") (pintype "passive"))
    )
    (net (code "109") (name "Net-(U2.Y-A)") (class "Default")
      (node (ref "LED2.Y") (pin "C") (pinfunction "C_C") (pintype "passive"))
      (node (ref "U2.Y") (pin "1") (pinfunction "A_1") (pintype "passive"))
    )
    (net (code "110") (name "Net-(U2.Z-A)") (class "Default")
      (node (ref "LED2.Z") (pin "C") (pinfunction "C_C") (pintype "passive"))
      (node (ref "U2.Z") (pin "1") (pinfunction "A_1") (pintype "passive"))
    )
    (net (code "111") (name "Net-(X1-5)") (class "Default")
      (node (ref "LED4") (pin "A") (pinfunction "A_A") (pintype "passive"))
      (node (ref "X1") (pin "P$5") (pinfunction "5_P$5") (pintype "passive"))
    )
    (net (code "112") (name "Net-(X1-6)") (class "Default")
      (node (ref "LED3") (pin "A") (pinfunction "A_A") (pintype "passive"))
      (node (ref "X1") (pin "P$6") (pinfunction "6_P$6") (pintype "passive"))
    )
    (net (code "113") (name "Net-(X1-7)") (class "Default")
      (node (ref "LED1") (pin "A") (pinfunction "A_A") (pintype "passive"))
      (node (ref "X1") (pin "P$7") (pinfunction "7_P$7") (pintype "passive"))
    )
    (net (code "114") (name "Net-(X1-8)") (class "Default")
      (node (ref "LED2") (pin "A") (pinfunction "A_A") (pintype "passive"))
      (node (ref "X1") (pin "P$8") (pinfunction "8_P$8") (pintype "passive"))
    )
    (net (code "115") (name "unconnected-(J1-Pad1)") (class "Default")
      (node (ref "J1") (pin "1") (pinfunction "1_1") (pintype "passive"))
    )
    (net (code "116") (name "unconnected-(J1-Pad2)") (class "Default")
      (node (ref "J1") (pin "2") (pinfunction "2_2") (pintype "passive"))
    )
    (net (code "117") (name "unconnected-(J1-Pad3)") (class "Default")
      (node (ref "J1") (pin "3") (pinfunction "3_3") (pintype "passive"))
    )
    (net (code "118") (name "unconnected-(J1-Pad4)") (class "Default")
      (node (ref "J1") (pin "4") (pinfunction "4_4") (pintype "passive"))
    )
    (net (code "119") (name "unconnected-(J1-Pad5)") (class "Default")
      (node (ref "J1") (pin "5") (pinfunction "5_5") (pintype "passive"))
    )
    (net (code "120") (name "unconnected-(J1-Pad6)") (class "Default")
      (node (ref "J1") (pin "6") (pinfunction "6_6") (pintype "passive"))
    )
    (net (code "121") (name "unconnected-(R1-Pad1)") (class "Default")
      (node (ref "R1") (pin "1") (pinfunction "1_1") (pintype "passive"))
    )
    (net (code "122") (name "unconnected-(R1-Pad2)") (class "Default")
      (node (ref "R1") (pin "2") (pinfunction "2_2") (pintype "passive"))
    )
  )
)
